# POWER.net
KiCad netlist of a schematic drawn in Altium Designer
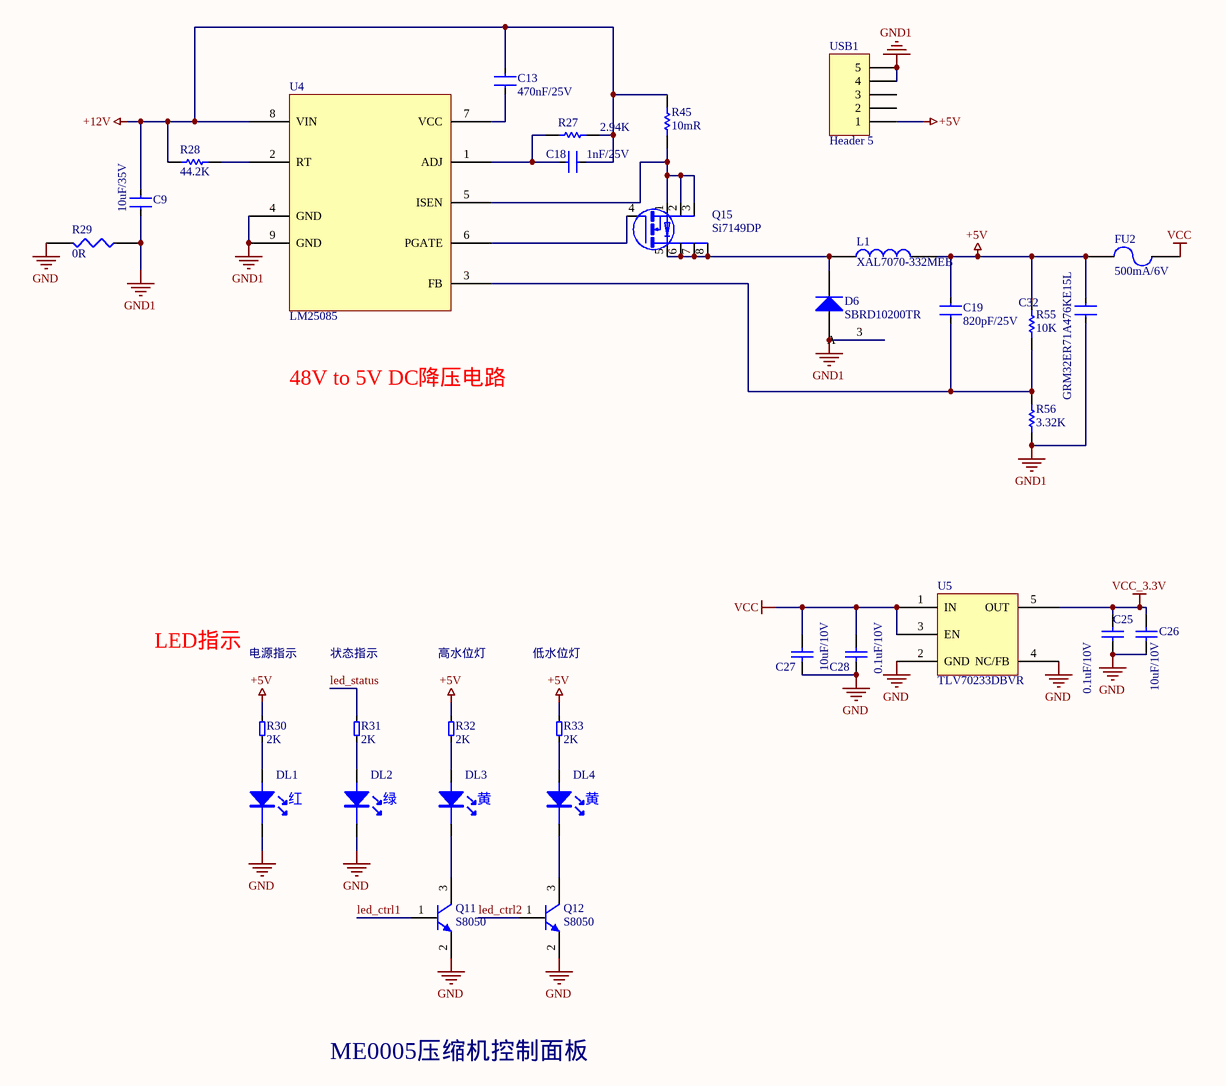
[diagram p0: POWER.SchDoc]

(export (version "E")
  (design (tool "Eeschema 10.0.6"))
  (components
    (comp (ref "C9")
      (value "10uF/35V")
      (footprint "1210C")
      (description "CCX85-103")
      (libsource (lib "无极性电容") (part "0.01UF"))
    )
    (comp (ref "C13")
      (value "470nF/25V")
      (footprint "0603C")
      (description "CCX85-103")
      (libsource (lib "无极性电容") (part "0.01UF"))
    )
    (comp (ref "C18")
      (value "1nF/25V")
      (footprint "0603C")
      (description "CCX85-103")
      (libsource (lib "无极性电容") (part "0.01UF"))
    )
    (comp (ref "C19")
      (value "820pF/25V")
      (footprint "0603C")
      (description "CCX85-103")
      (libsource (lib "无极性电容") (part "0.01UF"))
    )
    (comp (ref "C25")
      (value "0.1uF/10V")
      (footprint "0603C")
      (description "Capacitor")
      (fields (field (name "PUBLISHER") "Altium Limited"))
      (libsource (lib "Miscellaneous Devices") (part "Cap"))
    )
    (comp (ref "C26")
      (value "10uF/10V")
      (footprint "0603C")
      (description "Capacitor")
      (fields (field (name "PUBLISHER") "Altium Limited"))
      (libsource (lib "Miscellaneous Devices") (part "Cap"))
    )
    (comp (ref "C27")
      (value "10uF/10V")
      (footprint "0603C")
      (description "Capacitor")
      (fields (field (name "PUBLISHER") "Altium Limited"))
      (libsource (lib "Miscellaneous Devices") (part "Cap"))
    )
    (comp (ref "C28")
      (value "0.1uF/10V")
      (footprint "0603C")
      (description "Capacitor")
      (fields (field (name "PUBLISHER") "Altium Limited"))
      (libsource (lib "Miscellaneous Devices") (part "Cap"))
    )
    (comp (ref "C32")
      (value "GRM32ER71A476KE15L")
      (footprint "1210C")
      (description "CCX85-103")
      (libsource (lib "无极性电容") (part "0.01UF"))
    )
    (comp (ref "D6")
      (value "SBRD10200TR")
      (footprint "TO228P970-3N")
      (description "Default Diode")
      (fields (field (name "PUBLISHER") "Altium Limited"))
      (libsource (lib "SM") (part "Diode_2"))
    )
    (comp (ref "DL1")
      (value "红")
      (footprint "LED-3")
      (description "CP-L-7113SRD-D")
      (libsource (lib "光电器件") (part "L-7113SRD-D"))
    )
    (comp (ref "DL2")
      (value "绿")
      (footprint "LED-3")
      (description "CP-L-7113SRD-D")
      (libsource (lib "光电器件") (part "L-7113SRD-D"))
    )
    (comp (ref "DL3")
      (value "黄")
      (footprint "LED-3")
      (description "CP-L-7113SRD-D")
      (libsource (lib "光电器件") (part "L-7113SRD-D"))
    )
    (comp (ref "DL4")
      (value "黄")
      (footprint "LED-3")
      (description "CP-L-7113SRD-D")
      (libsource (lib "光电器件") (part "L-7113SRD-D"))
    )
    (comp (ref "FU2")
      (value "500mA/6V")
      (footprint "F0805")
      (description "Fuse")
      (libsource (lib "SM") (part "FUSE2"))
    )
    (comp (ref "L1") (value "XAL7070-332MEB") (footprint "XAL7070") (libsource (lib "*") (part "INDUCTOR")))
    (comp (ref "Q11")
      (value "S8050")
      (footprint "SOT23-3")
      (description "NPN Bipolar Transistor")
      (fields (field (name "PUBLISHER") "Altium Limited"))
      (libsource (lib "Miscellaneous Devices") (part "NPN"))
    )
    (comp (ref "Q12")
      (value "S8050")
      (footprint "SOT23-3")
      (description "NPN Bipolar Transistor")
      (fields (field (name "PUBLISHER") "Altium Limited"))
      (libsource (lib "Miscellaneous Devices") (part "NPN"))
    )
    (comp (ref "Q15")
      (value "Si7149DP")
      (footprint "PowerPAK SO-8")
      (description "Si4004DY")
      (libsource (lib "Schlib_20110825") (part "Si4004DY"))
    )
    (comp (ref "R27")
      (value "2.94K")
      (footprint "0603R")
      (description "Semiconductor Resistor")
      (fields (field (name "PUBLISHER") "Altium Limited"))
      (libsource (lib "Miscellaneous Devices") (part "Res Semi"))
    )
    (comp (ref "R28")
      (value "44.2K")
      (footprint "0603R")
      (description "Semiconductor Resistor")
      (fields (field (name "PUBLISHER") "Altium Limited"))
      (libsource (lib "Miscellaneous Devices") (part "Res Semi"))
    )
    (comp (ref "R29") (value "0R") (footprint "0805R") (libsource (lib "其他电阻") (part "RES1")))
    (comp (ref "R30")
      (value "2K")
      (footprint "0805R")
      (description "CR85-102J")
      (libsource (lib "SMD电阻") (part "1K"))
    )
    (comp (ref "R31")
      (value "2K")
      (footprint "0805R")
      (description "CR85-102J")
      (libsource (lib "SMD电阻") (part "1K"))
    )
    (comp (ref "R32")
      (value "2K")
      (footprint "0805R")
      (description "CR85-102J")
      (libsource (lib "SMD电阻") (part "1K"))
    )
    (comp (ref "R33")
      (value "2K")
      (footprint "0805R")
      (description "CR85-102J")
      (libsource (lib "SMD电阻") (part "1K"))
    )
    (comp (ref "R45")
      (value "10mR")
      (footprint "1206R")
      (description "Semiconductor Resistor")
      (fields (field (name "PUBLISHER") "Altium Limited"))
      (libsource (lib "Miscellaneous Devices") (part "Res Semi"))
    )
    (comp (ref "R55")
      (value "10K")
      (footprint "0603R")
      (description "Semiconductor Resistor")
      (fields (field (name "PUBLISHER") "Altium Limited"))
      (libsource (lib "Miscellaneous Devices") (part "Res Semi"))
    )
    (comp (ref "R56")
      (value "3.32K")
      (footprint "0603R")
      (description "Semiconductor Resistor")
      (fields (field (name "PUBLISHER") "Altium Limited"))
      (libsource (lib "Miscellaneous Devices") (part "Res Semi"))
    )
    (comp (ref "U4")
      (value "LM25085")
      (footprint "SOP65P490X265_HS-8N")
      (libsource (lib "Schlib_20110825") (part "LM25085"))
    )
    (comp (ref "U5")
      (value "TLV70233DBVR")
      (footprint "SOT23-5(DBV)")
      (libsource (lib "Schlib_20110825") (part "TLV70230DBVR"))
    )
    (comp (ref "USB1")
      (value "Header 5")
      (footprint "USB-A")
      (description "Header, 5-Pin")
      (fields (field (name "PUBLISHER") "Altium Limited"))
      (libsource (lib "Miscellaneous Connectors") (part "Header 5"))
    )
  )
  (nets
    (net (code "1") (name "+5V") (class "Default")
      (node (ref "C19") (pin "1") (pinfunction "1_1") (pintype "passive"))
      (node (ref "C32") (pin "1") (pinfunction "1_1") (pintype "passive"))
      (node (ref "FU2") (pin "1") (pinfunction "1_1") (pintype "passive"))
      (node (ref "L1") (pin "2") (pinfunction "2_2") (pintype "passive"))
      (node (ref "R30") (pin "2") (pinfunction "2_2") (pintype "passive"))
      (node (ref "R32") (pin "2") (pinfunction "2_2") (pintype "passive"))
      (node (ref "R33") (pin "2") (pinfunction "2_2") (pintype "passive"))
      (node (ref "R55") (pin "1") (pinfunction "1_1") (pintype "passive"))
      (node (ref "USB1") (pin "1") (pinfunction "1_1") (pintype "passive"))
    )
    (net (code "2") (name "+12V") (class "Default")
      (node (ref "C13") (pin "2") (pinfunction "2_2") (pintype "passive"))
      (node (ref "C18") (pin "1") (pinfunction "1_1") (pintype "passive"))
      (node (ref "C9") (pin "1") (pinfunction "1_1") (pintype "passive"))
      (node (ref "R27") (pin "1") (pinfunction "1_1") (pintype "passive"))
      (node (ref "R28") (pin "2") (pinfunction "2_2") (pintype "passive"))
      (node (ref "R45") (pin "1") (pinfunction "1_1") (pintype "passive"))
      (node (ref "U4") (pin "8") (pinfunction "VIN_8") (pintype "passive"))
    )
    (net (code "3") (name "/led_ctrl1") (class "Default")
      (node (ref "Q11") (pin "1") (pinfunction "B_1") (pintype "passive"))
    )
    (net (code "4") (name "/led_ctrl2") (class "Default")
      (node (ref "Q12") (pin "1") (pinfunction "B_1") (pintype "passive"))
    )
    (net (code "5") (name "/led_status") (class "Default")
      (node (ref "R31") (pin "2") (pinfunction "2_2") (pintype "passive"))
    )
    (net (code "6") (name "GND") (class "Default")
      (node (ref "C25") (pin "2") (pinfunction "2_2") (pintype "passive"))
      (node (ref "C26") (pin "1") (pinfunction "1_1") (pintype "passive"))
      (node (ref "C27") (pin "1") (pinfunction "1_1") (pintype "passive"))
      (node (ref "C28") (pin "2") (pinfunction "2_2") (pintype "passive"))
      (node (ref "DL1") (pin "K") (pinfunction "2_K") (pintype "passive"))
      (node (ref "DL2") (pin "K") (pinfunction "2_K") (pintype "passive"))
      (node (ref "Q11") (pin "2") (pinfunction "E_2") (pintype "passive"))
      (node (ref "Q12") (pin "2") (pinfunction "E_2") (pintype "passive"))
      (node (ref "R29") (pin "2") (pinfunction "2_2") (pintype "passive"))
      (node (ref "U5") (pin "2") (pinfunction "GND_2") (pintype "passive"))
      (node (ref "U5") (pin "4") (pinfunction "NC/FB_4") (pintype "passive"))
    )
    (net (code "7") (name "GND1") (class "Default")
      (node (ref "C32") (pin "2") (pinfunction "2_2") (pintype "passive"))
      (node (ref "C9") (pin "2") (pinfunction "2_2") (pintype "passive"))
      (node (ref "D6") (pin "1") (pinfunction "A_1") (pintype "passive"))
      (node (ref "D6") (pin "3") (pinfunction "A_3") (pintype "passive"))
      (node (ref "R29") (pin "1") (pinfunction "1_1") (pintype "passive"))
      (node (ref "R56") (pin "2") (pinfunction "2_2") (pintype "passive"))
      (node (ref "U4") (pin "4") (pinfunction "GND_4") (pintype "passive"))
      (node (ref "U4") (pin "9") (pinfunction "GND_9") (pintype "passive"))
      (node (ref "USB1") (pin "4") (pinfunction "4_4") (pintype "passive"))
      (node (ref "USB1") (pin "5") (pinfunction "5_5") (pintype "passive"))
    )
    (net (code "8") (name "Net-(D6-K)") (class "Default")
      (node (ref "D6") (pin "2") (pinfunction "K_2") (pintype "passive"))
      (node (ref "L1") (pin "1") (pinfunction "1_1") (pintype "passive"))
      (node (ref "Q15") (pin "5") (pinfunction "D_5") (pintype "passive"))
      (node (ref "Q15") (pin "6") (pinfunction "D_6") (pintype "passive"))
      (node (ref "Q15") (pin "7") (pinfunction "D_7") (pintype "passive"))
      (node (ref "Q15") (pin "8") (pinfunction "D_8") (pintype "passive"))
    )
    (net (code "9") (name "Net-(DL1-1)") (class "Default")
      (node (ref "DL1") (pin "A") (pinfunction "1_A") (pintype "passive"))
      (node (ref "R30") (pin "1") (pinfunction "1_1") (pintype "passive"))
    )
    (net (code "10") (name "Net-(DL2-1)") (class "Default")
      (node (ref "DL2") (pin "A") (pinfunction "1_A") (pintype "passive"))
      (node (ref "R31") (pin "1") (pinfunction "1_1") (pintype "passive"))
    )
    (net (code "11") (name "Net-(DL3-1)") (class "Default")
      (node (ref "DL3") (pin "A") (pinfunction "1_A") (pintype "passive"))
      (node (ref "R32") (pin "1") (pinfunction "1_1") (pintype "passive"))
    )
    (net (code "12") (name "Net-(DL3-2)") (class "Default")
      (node (ref "DL3") (pin "K") (pinfunction "2_K") (pintype "passive"))
      (node (ref "Q11") (pin "3") (pinfunction "C_3") (pintype "passive"))
    )
    (net (code "13") (name "Net-(DL4-1)") (class "Default")
      (node (ref "DL4") (pin "A") (pinfunction "1_A") (pintype "passive"))
      (node (ref "R33") (pin "1") (pinfunction "1_1") (pintype "passive"))
    )
    (net (code "14") (name "Net-(DL4-2)") (class "Default")
      (node (ref "DL4") (pin "K") (pinfunction "2_K") (pintype "passive"))
      (node (ref "Q12") (pin "3") (pinfunction "C_3") (pintype "passive"))
    )
    (net (code "15") (name "Net-(Q15-G)") (class "Default")
      (node (ref "Q15") (pin "4") (pinfunction "G_4") (pintype "passive"))
      (node (ref "U4") (pin "6") (pinfunction "PGATE_6") (pintype "passive"))
    )
    (net (code "16") (name "Net-(U4-ADJ)") (class "Default")
      (node (ref "C18") (pin "2") (pinfunction "2_2") (pintype "passive"))
      (node (ref "R27") (pin "2") (pinfunction "2_2") (pintype "passive"))
      (node (ref "U4") (pin "1") (pinfunction "ADJ_1") (pintype "passive"))
    )
    (net (code "17") (name "Net-(U4-FB)") (class "Default")
      (node (ref "C19") (pin "2") (pinfunction "2_2") (pintype "passive"))
      (node (ref "R55") (pin "2") (pinfunction "2_2") (pintype "passive"))
      (node (ref "R56") (pin "1") (pinfunction "1_1") (pintype "passive"))
      (node (ref "U4") (pin "3") (pinfunction "FB_3") (pintype "passive"))
    )
    (net (code "18") (name "Net-(U4-ISEN)") (class "Default")
      (node (ref "Q15") (pin "1") (pinfunction "S_1") (pintype "passive"))
      (node (ref "Q15") (pin "2") (pinfunction "S_2") (pintype "passive"))
      (node (ref "Q15") (pin "3") (pinfunction "S_3") (pintype "passive"))
      (node (ref "R45") (pin "2") (pinfunction "2_2") (pintype "passive"))
      (node (ref "U4") (pin "5") (pinfunction "ISEN_5") (pintype "passive"))
    )
    (net (code "19") (name "Net-(U4-RT)") (class "Default")
      (node (ref "R28") (pin "1") (pinfunction "1_1") (pintype "passive"))
      (node (ref "U4") (pin "2") (pinfunction "RT_2") (pintype "passive"))
    )
    (net (code "20") (name "Net-(U4-VCC)") (class "Default")
      (node (ref "C13") (pin "1") (pinfunction "1_1") (pintype "passive"))
      (node (ref "U4") (pin "7") (pinfunction "VCC_7") (pintype "passive"))
    )
    (net (code "21") (name "VCC") (class "Default")
      (node (ref "C27") (pin "2") (pinfunction "2_2") (pintype "passive"))
      (node (ref "C28") (pin "1") (pinfunction "1_1") (pintype "passive"))
      (node (ref "FU2") (pin "2") (pinfunction "2_2") (pintype "passive"))
      (node (ref "U5") (pin "1") (pinfunction "IN_1") (pintype "passive"))
      (node (ref "U5") (pin "3") (pinfunction "EN_3") (pintype "passive"))
    )
    (net (code "22") (name "VCC_3.3V") (class "Default")
      (node (ref "C25") (pin "1") (pinfunction "1_1") (pintype "passive"))
      (node (ref "C26") (pin "2") (pinfunction "2_2") (pintype "passive"))
      (node (ref "U5") (pin "5") (pinfunction "OUT_5") (pintype "passive"))
    )
    (net (code "23") (name "unconnected-(USB1-Pad2)") (class "Default")
      (node (ref "USB1") (pin "2") (pinfunction "2_2") (pintype "passive"))
    )
    (net (code "24") (name "unconnected-(USB1-Pad3)") (class "Default")
      (node (ref "USB1") (pin "3") (pinfunction "3_3") (pintype "passive"))
    )
  )
)
